# MRAM.net
KiCad netlist of a schematic drawn in Altium Designer
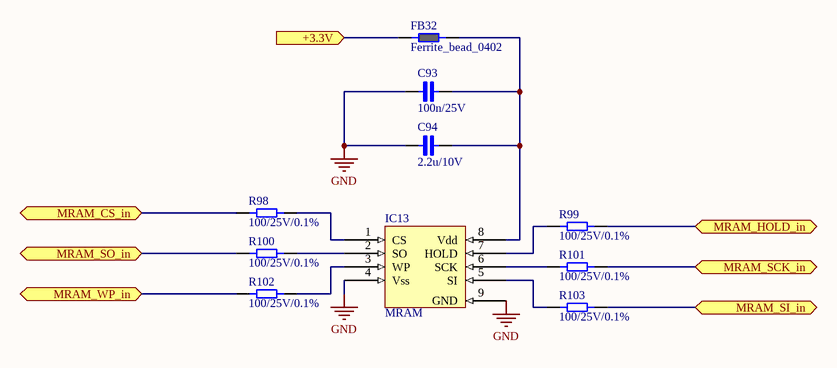
[diagram p0: MRAM.SchDoc]

(export (version "E")
  (design (tool "Eeschema 10.0.6"))
  (components
    (comp (ref "C93")
      (value "100n/25V")
      (footprint "Cap_0402")
      (description "Ceramic Capacitor 100n / 0402 / 25V / ±5%, Wurth Elektronik MLCC")
      (libsource (lib "Cubesat_lib") (part "Cap_0402_100n"))
    )
    (comp (ref "C94")
      (value "2.2u/10V")
      (footprint "CAP_0603")
      (description "Ceramic Capacitor 2.2uF / 0603 / 10V / ±5%, Wurth Elektronik MLCC")
      (libsource (lib "Cubesat_lib") (part "Cap_0603_2.2u"))
    )
    (comp (ref "FB32")
      (value "Ferrite_bead_0402")
      (footprint "FERRITE_0402")
      (description "Ferrite bead, wurth 74269241102")
      (libsource (lib "Cubesat_lib") (part "Ferrite_bead_0402"))
    )
    (comp (ref "IC13")
      (value "MRAM")
      (footprint "DFN8")
      (description "MRAM, 128Kb Serial SPI MRAM, EVERPIN technologies")
      (libsource (lib "Cubesat_lib") (part "MR25H128A"))
    )
    (comp (ref "R98")
      (value "100/25V/0.1%")
      (footprint "RES_0402")
      (description "Vishay, thin film resistor 100/25V/0.1%")
      (libsource (lib "Cubesat_lib") (part "Res_0402_100"))
    )
    (comp (ref "R99")
      (value "100/25V/0.1%")
      (footprint "RES_0402")
      (description "Vishay, thin film resistor 100/25V/0.1%")
      (libsource (lib "Cubesat_lib") (part "Res_0402_100"))
    )
    (comp (ref "R100")
      (value "100/25V/0.1%")
      (footprint "RES_0402")
      (description "Vishay, thin film resistor 100/25V/0.1%")
      (libsource (lib "Cubesat_lib") (part "Res_0402_100"))
    )
    (comp (ref "R101")
      (value "100/25V/0.1%")
      (footprint "RES_0402")
      (description "Vishay, thin film resistor 100/25V/0.1%")
      (libsource (lib "Cubesat_lib") (part "Res_0402_100"))
    )
    (comp (ref "R102")
      (value "100/25V/0.1%")
      (footprint "RES_0402")
      (description "Vishay, thin film resistor 100/25V/0.1%")
      (libsource (lib "Cubesat_lib") (part "Res_0402_100"))
    )
    (comp (ref "R103")
      (value "100/25V/0.1%")
      (footprint "RES_0402")
      (description "Vishay, thin film resistor 100/25V/0.1%")
      (libsource (lib "Cubesat_lib") (part "Res_0402_100"))
    )
  )
  (nets
    (net (code "1") (name "/+3.3V") (class "Default")
      (node (ref "FB32") (pin "1") (pinfunction "1_1") (pintype "passive"))
    )
    (net (code "2") (name "/MRAM_CS_in") (class "Default")
      (node (ref "R98") (pin "1") (pinfunction "1_1") (pintype "passive"))
    )
    (net (code "3") (name "/MRAM_HOLD_in") (class "Default")
      (node (ref "R99") (pin "2") (pinfunction "2_2") (pintype "passive"))
    )
    (net (code "4") (name "/MRAM_SCK_in") (class "Default")
      (node (ref "R101") (pin "2") (pinfunction "2_2") (pintype "passive"))
    )
    (net (code "5") (name "/MRAM_SI_in") (class "Default")
      (node (ref "R103") (pin "2") (pinfunction "2_2") (pintype "passive"))
    )
    (net (code "6") (name "/MRAM_SO_in") (class "Default")
      (node (ref "R100") (pin "1") (pinfunction "1_1") (pintype "passive"))
    )
    (net (code "7") (name "/MRAM_WP_in") (class "Default")
      (node (ref "R102") (pin "1") (pinfunction "1_1") (pintype "passive"))
    )
    (net (code "8") (name "GND") (class "Default")
      (node (ref "C93") (pin "1") (pinfunction "1_1") (pintype "passive"))
      (node (ref "C94") (pin "1") (pinfunction "1_1") (pintype "passive"))
      (node (ref "IC13") (pin "4") (pinfunction "Vss_4") (pintype "input"))
      (node (ref "IC13") (pin "9") (pinfunction "GND_9") (pintype "input"))
    )
    (net (code "9") (name "Net-(IC13-CS)") (class "Default")
      (node (ref "IC13") (pin "1") (pinfunction "CS_1") (pintype "input"))
      (node (ref "R98") (pin "2") (pinfunction "2_2") (pintype "passive"))
    )
    (net (code "10") (name "Net-(IC13-HOLD)") (class "Default")
      (node (ref "IC13") (pin "7") (pinfunction "HOLD_7") (pintype "input"))
      (node (ref "R99") (pin "1") (pinfunction "1_1") (pintype "passive"))
    )
    (net (code "11") (name "Net-(IC13-SCK)") (class "Default")
      (node (ref "IC13") (pin "6") (pinfunction "SCK_6") (pintype "input"))
      (node (ref "R101") (pin "1") (pinfunction "1_1") (pintype "passive"))
    )
    (net (code "12") (name "Net-(IC13-SI)") (class "Default")
      (node (ref "IC13") (pin "5") (pinfunction "SI_5") (pintype "input"))
      (node (ref "R103") (pin "1") (pinfunction "1_1") (pintype "passive"))
    )
    (net (code "13") (name "Net-(IC13-SO)") (class "Default")
      (node (ref "IC13") (pin "2") (pinfunction "SO_2") (pintype "input"))
      (node (ref "R100") (pin "2") (pinfunction "2_2") (pintype "passive"))
    )
    (net (code "14") (name "Net-(IC13-Vdd)") (class "Default")
      (node (ref "C93") (pin "2") (pinfunction "2_2") (pintype "passive"))
      (node (ref "C94") (pin "2") (pinfunction "2_2") (pintype "passive"))
      (node (ref "FB32") (pin "2") (pinfunction "2_2") (pintype "passive"))
      (node (ref "IC13") (pin "8") (pinfunction "Vdd_8") (pintype "input"))
    )
    (net (code "15") (name "Net-(IC13-WP)") (class "Default")
      (node (ref "IC13") (pin "3") (pinfunction "WP_3") (pintype "input"))
      (node (ref "R102") (pin "2") (pinfunction "2_2") (pintype "passive"))
    )
  )
)
